# BatteryCheck.net
KiCad netlist of a schematic drawn in Altium Designer
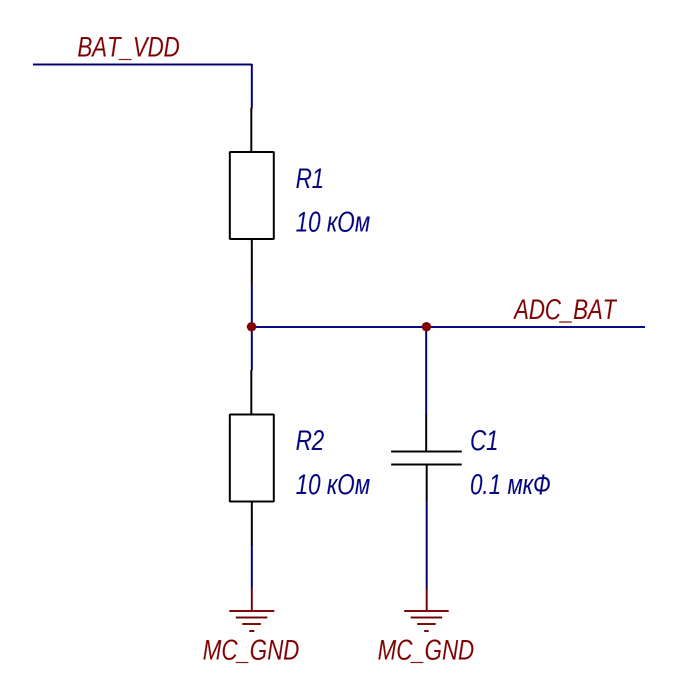
[diagram p0: BatteryCheck.SchDoc]

(export (version "E")
  (design (tool "Eeschema 10.0.6"))
  (components
    (comp (ref "C1")
      (value "0.1 мкФ")
      (footprint "C 0805")
      (description "SMD Capacitor 0805")
      (fields
        (field (name "TOLERANCE") "/Укажите допуск в процентах/")
        (field (name "MANUFACTURER") "/Укажите компанию-производителя/")
      )
      (libsource (lib "my_lib") (part "CAP 0805"))
    )
    (comp (ref "R1") (value "10 кОм") (footprint "RES 0402") (libsource (lib "my_lib") (part "RES 0402")))
    (comp (ref "R2") (value "10 кОм") (footprint "RES 0402") (libsource (lib "my_lib") (part "RES 0402")))
  )
  (nets
    (net (code "1") (name "/ADC_BAT") (class "Default")
      (node (ref "C1") (pin "1") (pinfunction "1_1") (pintype "passive"))
      (node (ref "R1") (pin "1") (pinfunction "1_1") (pintype "passive"))
      (node (ref "R2") (pin "2") (pinfunction "2_2") (pintype "passive"))
    )
    (net (code "2") (name "/BAT_VDD") (class "Default")
      (node (ref "R1") (pin "2") (pinfunction "2_2") (pintype "passive"))
    )
    (net (code "3") (name "MC_GND") (class "Default")
      (node (ref "C1") (pin "2") (pinfunction "2_2") (pintype "passive"))
      (node (ref "R2") (pin "1") (pinfunction "1_1") (pintype "passive"))
    )
  )
)
